# camadapter.net
KiCad netlist of a schematic drawn in Altium Designer
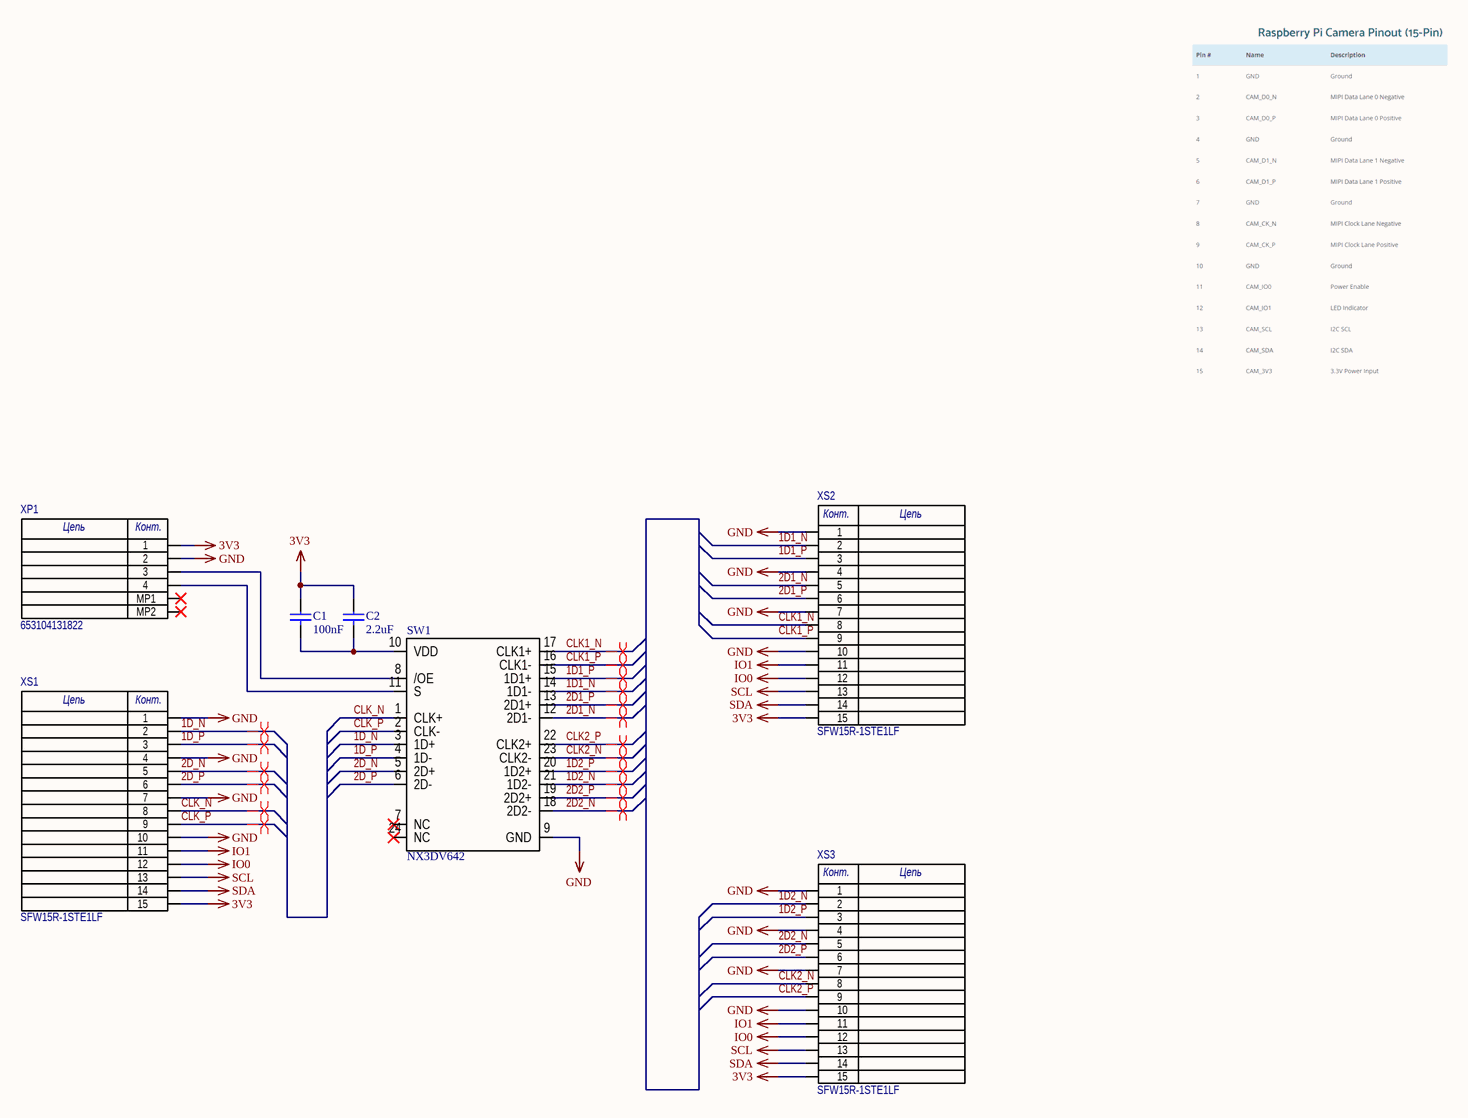
[diagram p0: camadapter.SchDoc]

(export (version "E")
  (design (tool "Eeschema 10.0.6"))
  (components
    (comp (ref "C1")
      (value "100nF")
      (footprint "Cap_0402_N")
      (description "Capacitor")
      (fields (field (name "PART NUMBER") "Capacitor 0402"))
      (libsource (lib "Purikov") (part "Cap_0402"))
    )
    (comp (ref "C2")
      (value "2.2uF")
      (footprint "Cap_0402_N")
      (description "Capacitor")
      (fields (field (name "PART NUMBER") "Capacitor 0402"))
      (libsource (lib "Purikov") (part "Cap_0402"))
    )
    (comp (ref "SW1") (value "NX3DV642") (footprint "NX3DV642") (libsource (lib "Schlib") (part "NX3DV642")))
    (comp (ref "XP1")
      (value "653104131822")
      (footprint "653104131822_D_arch")
      (description "Header, Pins, 4 Contacts, SMD, R/A, 0,049\" (1,25mm).")
      (libsource (lib "ConnectorsDb") (part "653104131822"))
    )
    (comp (ref "XS1")
      (value "SFW15R-1STE1LF")
      (footprint "SFW15R-1STE1LF_D")
      (description "FFC-FPC Connector, 15 Contacts, SMD, R/A, 0.039\" (1.00mm).")
      (libsource (lib "ConnectorsDb") (part "SFW15R-1STE1LF"))
    )
    (comp (ref "XS2")
      (value "SFW15R-1STE1LF")
      (footprint "SFW15R-1STE1LF_D")
      (description "FFC-FPC Connector, 15 Contacts, SMD, R/A, 0.039\" (1.00mm).")
      (libsource (lib "ConnectorsDb") (part "SFW15R-1STE1LF"))
    )
    (comp (ref "XS3")
      (value "SFW15R-1STE1LF")
      (footprint "SFW15R-1STE1LF_D")
      (description "FFC-FPC Connector, 15 Contacts, SMD, R/A, 0.039\" (1.00mm).")
      (libsource (lib "ConnectorsDb") (part "SFW15R-1STE1LF"))
    )
  )
  (nets
    (net (code "1") (name "/1D1_N") (class "Default")
      (node (ref "SW1") (pin "14") (pinfunction "1D1-_14") (pintype "passive"))
      (node (ref "XS2") (pin "2") (pinfunction "2_2") (pintype "passive"))
    )
    (net (code "2") (name "/1D1_P") (class "Default")
      (node (ref "SW1") (pin "15") (pinfunction "1D1+_15") (pintype "passive"))
      (node (ref "XS2") (pin "3") (pinfunction "3_3") (pintype "passive"))
    )
    (net (code "3") (name "/1D2_N") (class "Default")
      (node (ref "SW1") (pin "21") (pinfunction "1D2-_21") (pintype "passive"))
      (node (ref "XS3") (pin "2") (pinfunction "2_2") (pintype "passive"))
    )
    (net (code "4") (name "/1D2_P") (class "Default")
      (node (ref "SW1") (pin "20") (pinfunction "1D2+_20") (pintype "passive"))
      (node (ref "XS3") (pin "3") (pinfunction "3_3") (pintype "passive"))
    )
    (net (code "5") (name "/1D_N") (class "Default")
      (node (ref "SW1") (pin "3") (pinfunction "1D+_3") (pintype "passive"))
      (node (ref "XS1") (pin "2") (pinfunction "2_2") (pintype "passive"))
    )
    (net (code "6") (name "/1D_P") (class "Default")
      (node (ref "SW1") (pin "4") (pinfunction "1D-_4") (pintype "passive"))
      (node (ref "XS1") (pin "3") (pinfunction "3_3") (pintype "passive"))
    )
    (net (code "7") (name "/2D1_N") (class "Default")
      (node (ref "SW1") (pin "12") (pinfunction "2D1-_12") (pintype "passive"))
      (node (ref "XS2") (pin "5") (pinfunction "5_5") (pintype "passive"))
    )
    (net (code "8") (name "/2D1_P") (class "Default")
      (node (ref "SW1") (pin "13") (pinfunction "2D1+_13") (pintype "passive"))
      (node (ref "XS2") (pin "6") (pinfunction "6_6") (pintype "passive"))
    )
    (net (code "9") (name "/2D2_N") (class "Default")
      (node (ref "SW1") (pin "18") (pinfunction "2D2-_18") (pintype "passive"))
      (node (ref "XS3") (pin "5") (pinfunction "5_5") (pintype "passive"))
    )
    (net (code "10") (name "/2D2_P") (class "Default")
      (node (ref "SW1") (pin "19") (pinfunction "2D2+_19") (pintype "passive"))
      (node (ref "XS3") (pin "6") (pinfunction "6_6") (pintype "passive"))
    )
    (net (code "11") (name "/2D_N") (class "Default")
      (node (ref "SW1") (pin "5") (pinfunction "2D+_5") (pintype "passive"))
      (node (ref "XS1") (pin "5") (pinfunction "5_5") (pintype "passive"))
    )
    (net (code "12") (name "/2D_P") (class "Default")
      (node (ref "SW1") (pin "6") (pinfunction "2D-_6") (pintype "passive"))
      (node (ref "XS1") (pin "6") (pinfunction "6_6") (pintype "passive"))
    )
    (net (code "13") (name "/CLK1_N") (class "Default")
      (node (ref "SW1") (pin "17") (pinfunction "CLK1+_17") (pintype "passive"))
      (node (ref "XS2") (pin "8") (pinfunction "8_8") (pintype "passive"))
    )
    (net (code "14") (name "/CLK1_P") (class "Default")
      (node (ref "SW1") (pin "16") (pinfunction "CLK1-_16") (pintype "passive"))
      (node (ref "XS2") (pin "9") (pinfunction "9_9") (pintype "passive"))
    )
    (net (code "15") (name "/CLK2_N") (class "Default")
      (node (ref "SW1") (pin "23") (pinfunction "CLK2-_23") (pintype "passive"))
      (node (ref "XS3") (pin "8") (pinfunction "8_8") (pintype "passive"))
    )
    (net (code "16") (name "/CLK2_P") (class "Default")
      (node (ref "SW1") (pin "22") (pinfunction "CLK2+_22") (pintype "passive"))
      (node (ref "XS3") (pin "9") (pinfunction "9_9") (pintype "passive"))
    )
    (net (code "17") (name "/CLK_N") (class "Default")
      (node (ref "SW1") (pin "1") (pinfunction "CLK+_1") (pintype "passive"))
      (node (ref "XS1") (pin "8") (pinfunction "8_8") (pintype "passive"))
    )
    (net (code "18") (name "/CLK_P") (class "Default")
      (node (ref "SW1") (pin "2") (pinfunction "CLK-_2") (pintype "passive"))
      (node (ref "XS1") (pin "9") (pinfunction "9_9") (pintype "passive"))
    )
    (net (code "19") (name "3V3") (class "Default")
      (node (ref "C1") (pin "2") (pinfunction "2_2") (pintype "passive"))
      (node (ref "C2") (pin "2") (pinfunction "2_2") (pintype "passive"))
      (node (ref "XP1") (pin "1") (pinfunction "1_1") (pintype "passive"))
      (node (ref "XS1") (pin "15") (pinfunction "15_15") (pintype "passive"))
      (node (ref "XS2") (pin "15") (pinfunction "15_15") (pintype "passive"))
      (node (ref "XS3") (pin "15") (pinfunction "15_15") (pintype "passive"))
    )
    (net (code "20") (name "GND") (class "Default")
      (node (ref "SW1") (pin "9") (pinfunction "GND_9") (pintype "passive"))
      (node (ref "XP1") (pin "2") (pinfunction "2_2") (pintype "passive"))
      (node (ref "XS1") (pin "1") (pinfunction "1_1") (pintype "passive"))
      (node (ref "XS1") (pin "10") (pinfunction "10_10") (pintype "passive"))
      (node (ref "XS1") (pin "4") (pinfunction "4_4") (pintype "passive"))
      (node (ref "XS1") (pin "7") (pinfunction "7_7") (pintype "passive"))
      (node (ref "XS2") (pin "1") (pinfunction "1_1") (pintype "passive"))
      (node (ref "XS2") (pin "10") (pinfunction "10_10") (pintype "passive"))
      (node (ref "XS2") (pin "4") (pinfunction "4_4") (pintype "passive"))
      (node (ref "XS2") (pin "7") (pinfunction "7_7") (pintype "passive"))
      (node (ref "XS3") (pin "1") (pinfunction "1_1") (pintype "passive"))
      (node (ref "XS3") (pin "10") (pinfunction "10_10") (pintype "passive"))
      (node (ref "XS3") (pin "4") (pinfunction "4_4") (pintype "passive"))
      (node (ref "XS3") (pin "7") (pinfunction "7_7") (pintype "passive"))
    )
    (net (code "21") (name "IO0") (class "Default")
      (node (ref "XS1") (pin "12") (pinfunction "12_12") (pintype "passive"))
      (node (ref "XS2") (pin "12") (pinfunction "12_12") (pintype "passive"))
      (node (ref "XS3") (pin "12") (pinfunction "12_12") (pintype "passive"))
    )
    (net (code "22") (name "IO1") (class "Default")
      (node (ref "XS1") (pin "11") (pinfunction "11_11") (pintype "passive"))
      (node (ref "XS2") (pin "11") (pinfunction "11_11") (pintype "passive"))
      (node (ref "XS3") (pin "11") (pinfunction "11_11") (pintype "passive"))
    )
    (net (code "23") (name "Net-(SW1-S)") (class "Default")
      (node (ref "SW1") (pin "11") (pinfunction "S_11") (pintype "passive"))
      (node (ref "XP1") (pin "4") (pinfunction "4_4") (pintype "passive"))
    )
    (net (code "24") (name "Net-(SW1-VDD)") (class "Default")
      (node (ref "C1") (pin "1") (pinfunction "1_1") (pintype "passive"))
      (node (ref "C2") (pin "1") (pinfunction "1_1") (pintype "passive"))
      (node (ref "SW1") (pin "10") (pinfunction "VDD_10") (pintype "passive"))
    )
    (net (code "25") (name "Net-(SW1-{slash}OE)") (class "Default")
      (node (ref "SW1") (pin "8") (pinfunction "/OE_8") (pintype "passive"))
      (node (ref "XP1") (pin "3") (pinfunction "3_3") (pintype "passive"))
    )
    (net (code "26") (name "SCL") (class "Default")
      (node (ref "XS1") (pin "13") (pinfunction "13_13") (pintype "passive"))
      (node (ref "XS2") (pin "13") (pinfunction "13_13") (pintype "passive"))
      (node (ref "XS3") (pin "13") (pinfunction "13_13") (pintype "passive"))
    )
    (net (code "27") (name "SDA") (class "Default")
      (node (ref "XS1") (pin "14") (pinfunction "14_14") (pintype "passive"))
      (node (ref "XS2") (pin "14") (pinfunction "14_14") (pintype "passive"))
      (node (ref "XS3") (pin "14") (pinfunction "14_14") (pintype "passive"))
    )
    (net (code "28") (name "unconnected-(SW1-NC-Pad7)") (class "Default")
      (node (ref "SW1") (pin "7") (pinfunction "NC_7") (pintype "passive+no_connect"))
    )
    (net (code "29") (name "unconnected-(SW1-NC-Pad24)") (class "Default")
      (node (ref "SW1") (pin "24") (pinfunction "NC_24") (pintype "passive+no_connect"))
    )
    (net (code "30") (name "unconnected-(XP1-PadMP1)") (class "Default")
      (node (ref "XP1") (pin "MP1") (pinfunction "MP1_MP1") (pintype "passive+no_connect"))
    )
    (net (code "31") (name "unconnected-(XP1-PadMP2)") (class "Default")
      (node (ref "XP1") (pin "MP2") (pinfunction "MP2_MP2") (pintype "passive+no_connect"))
    )
  )
)
